# 001_MCU.net
KiCad netlist of a schematic drawn in Altium Designer
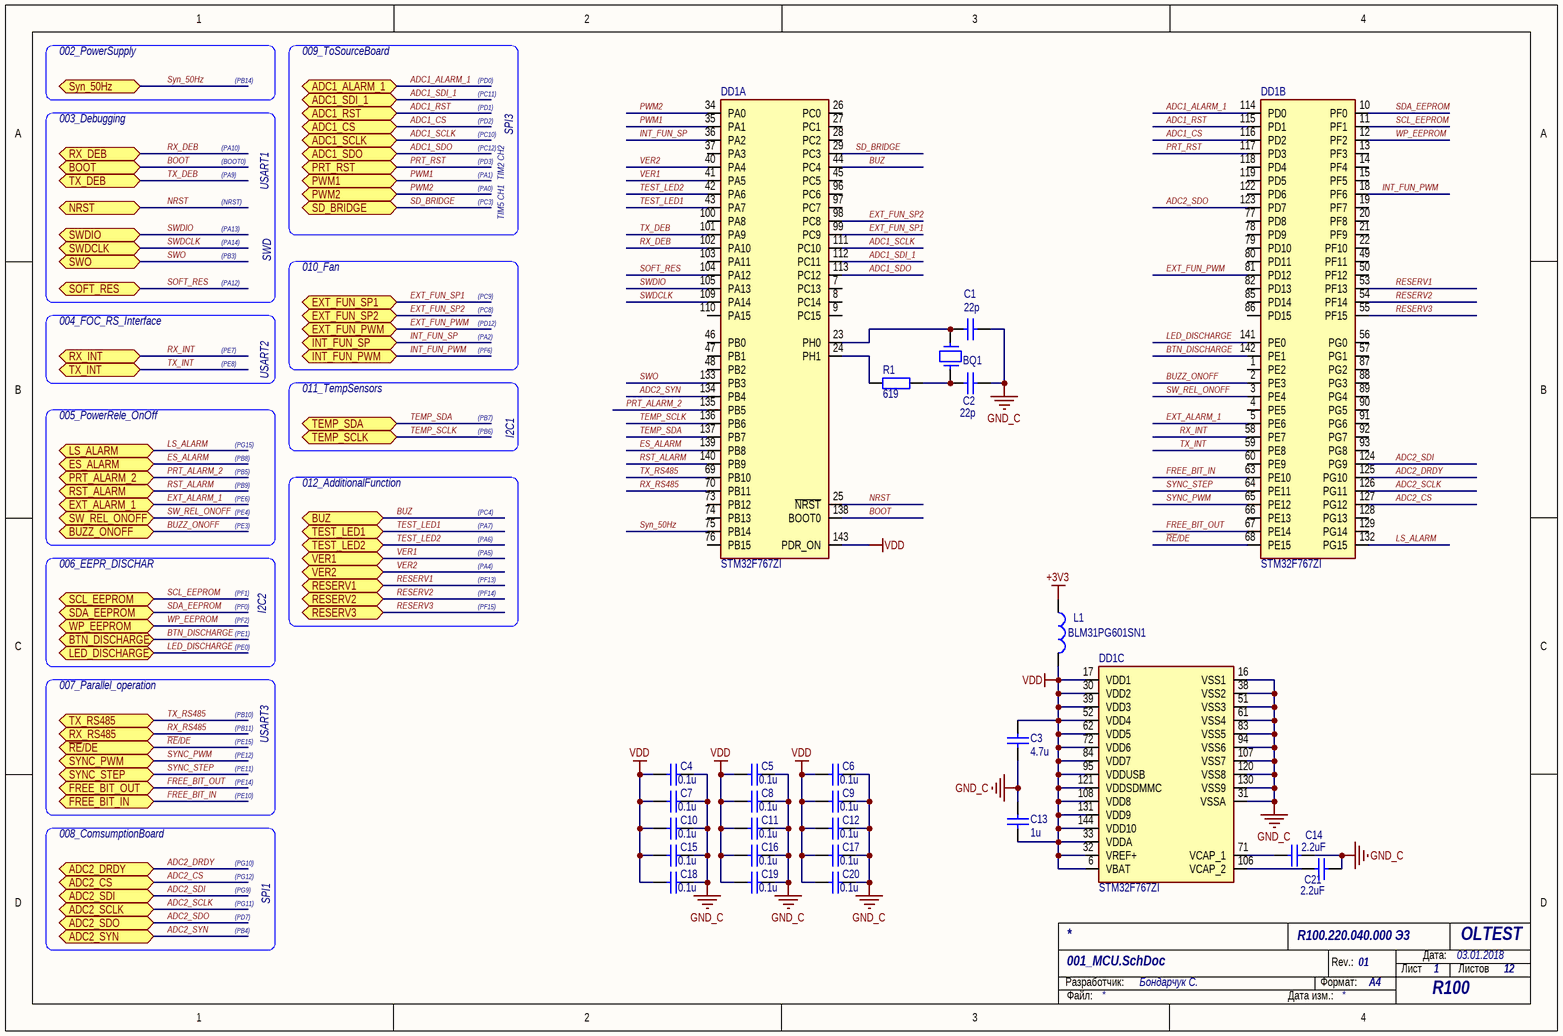
[diagram p0: 001_MCU.SchDoc]

(export (version "E")
  (design (tool "Eeschema 10.0.6"))
  (components
    (comp (ref "BQ1")
      (value "12MHz")
      (footprint "mainLib:DFN390P500X135-2N")
      (description "12MHz Quartz Crystal 7A")
      (fields (field (name "PARTNUMBER") "7A-12.000MAAJ-T") (field (name "MANUFACTURER") "TXC"))
      (libsource (lib "mainLib") (part "7A-12.000MAAJ-T"))
    )
    (comp (ref "C1")
      (value "22р")
      (footprint "mainLib:SMD_C_0603")
      (description "SMD C 0603 MURATA 50V 5% C0G")
      (fields (field (name "PARTNUMBER") "GRM1885C1H220JA01") (field (name "MANUFACTURER") "MURATA"))
      (libsource (lib "mainRCLib") (part "C0603 22p 50V 5%"))
    )
    (comp (ref "C2")
      (value "22р")
      (footprint "mainLib:SMD_C_0603")
      (description "SMD C 0603 MURATA 50V 5% C0G")
      (fields (field (name "PARTNUMBER") "GRM1885C1H220JA01") (field (name "MANUFACTURER") "MURATA"))
      (libsource (lib "mainRCLib") (part "C0603 22p 50V 5%"))
    )
    (comp (ref "C3")
      (value "4.7u")
      (footprint "mainLib:SMD_C_0805")
      (description "SMD C 0805 MURATA 50V 5% NP0")
      (fields (field (name "PARTNUMBER") "GRM21BR61E475M") (field (name "MANUFACTURER") "MURATA"))
      (libsource (lib "mainRCLib") (part "C0805 4.7u 25V 20%  X5R"))
    )
    (comp (ref "C4")
      (value "0.1u")
      (footprint "mainLib:SMD_C_0603")
      (description "SMD C 0603 MURATA 50V 10% X7R")
      (fields (field (name "PARTNUMBER") "GRM188R71H104K") (field (name "MANUFACTURER") "MURATA"))
      (libsource (lib "mainRCLib") (part "C0603 0.1u 50V 10%"))
    )
    (comp (ref "C5")
      (value "0.1u")
      (footprint "mainLib:SMD_C_0603")
      (description "SMD C 0603 MURATA 50V 10% X7R")
      (fields (field (name "PARTNUMBER") "GRM188R71H104K") (field (name "MANUFACTURER") "MURATA"))
      (libsource (lib "mainRCLib") (part "C0603 0.1u 50V 10%"))
    )
    (comp (ref "C6")
      (value "0.1u")
      (footprint "mainLib:SMD_C_0603")
      (description "SMD C 0603 MURATA 50V 10% X7R")
      (fields (field (name "PARTNUMBER") "GRM188R71H104K") (field (name "MANUFACTURER") "MURATA"))
      (libsource (lib "mainRCLib") (part "C0603 0.1u 50V 10%"))
    )
    (comp (ref "C7")
      (value "0.1u")
      (footprint "mainLib:SMD_C_0603")
      (description "SMD C 0603 MURATA 50V 10% X7R")
      (fields (field (name "PARTNUMBER") "GRM188R71H104K") (field (name "MANUFACTURER") "MURATA"))
      (libsource (lib "mainRCLib") (part "C0603 0.1u 50V 10%"))
    )
    (comp (ref "C8")
      (value "0.1u")
      (footprint "mainLib:SMD_C_0603")
      (description "SMD C 0603 MURATA 50V 10% X7R")
      (fields (field (name "PARTNUMBER") "GRM188R71H104K") (field (name "MANUFACTURER") "MURATA"))
      (libsource (lib "mainRCLib") (part "C0603 0.1u 50V 10%"))
    )
    (comp (ref "C9")
      (value "0.1u")
      (footprint "mainLib:SMD_C_0603")
      (description "SMD C 0603 MURATA 50V 10% X7R")
      (fields (field (name "PARTNUMBER") "GRM188R71H104K") (field (name "MANUFACTURER") "MURATA"))
      (libsource (lib "mainRCLib") (part "C0603 0.1u 50V 10%"))
    )
    (comp (ref "C10")
      (value "0.1u")
      (footprint "mainLib:SMD_C_0603")
      (description "SMD C 0603 MURATA 50V 10% X7R")
      (fields (field (name "PARTNUMBER") "GRM188R71H104K") (field (name "MANUFACTURER") "MURATA"))
      (libsource (lib "mainRCLib") (part "C0603 0.1u 50V 10%"))
    )
    (comp (ref "C11")
      (value "0.1u")
      (footprint "mainLib:SMD_C_0603")
      (description "SMD C 0603 MURATA 50V 10% X7R")
      (fields (field (name "PARTNUMBER") "GRM188R71H104K") (field (name "MANUFACTURER") "MURATA"))
      (libsource (lib "mainRCLib") (part "C0603 0.1u 50V 10%"))
    )
    (comp (ref "C12")
      (value "0.1u")
      (footprint "mainLib:SMD_C_0603")
      (description "SMD C 0603 MURATA 50V 10% X7R")
      (fields (field (name "PARTNUMBER") "GRM188R71H104K") (field (name "MANUFACTURER") "MURATA"))
      (libsource (lib "mainRCLib") (part "C0603 0.1u 50V 10%"))
    )
    (comp (ref "C13")
      (value "1u")
      (footprint "mainLib:SMD_C_0603")
      (description "SMD C 0603 MURATA 25V 10% X7R")
      (fields (field (name "PARTNUMBER") "GRM188R71E105KA12") (field (name "MANUFACTURER") "MURATA"))
      (libsource (lib "mainRCLib") (part "C0603 1uF 25V 10%"))
    )
    (comp (ref "C14")
      (value "2.2uF")
      (footprint "mainLib:SMD_C_0805")
      (description "SMD C 0805 MURATA 25V 10% X7R")
      (fields (field (name "PARTNUMBER") "GRM21BR61H225M") (field (name "MANUFACTURER") "MURATA"))
      (libsource (lib "mainRCLib") (part "C0805 2.2u 25V 10% X7R"))
    )
    (comp (ref "C15")
      (value "0.1u")
      (footprint "mainLib:SMD_C_0603")
      (description "SMD C 0603 MURATA 50V 10% X7R")
      (fields (field (name "PARTNUMBER") "GRM188R71H104K") (field (name "MANUFACTURER") "MURATA"))
      (libsource (lib "mainRCLib") (part "C0603 0.1u 50V 10%"))
    )
    (comp (ref "C16")
      (value "0.1u")
      (footprint "mainLib:SMD_C_0603")
      (description "SMD C 0603 MURATA 50V 10% X7R")
      (fields (field (name "PARTNUMBER") "GRM188R71H104K") (field (name "MANUFACTURER") "MURATA"))
      (libsource (lib "mainRCLib") (part "C0603 0.1u 50V 10%"))
    )
    (comp (ref "C17")
      (value "0.1u")
      (footprint "mainLib:SMD_C_0603")
      (description "SMD C 0603 MURATA 50V 10% X7R")
      (fields (field (name "PARTNUMBER") "GRM188R71H104K") (field (name "MANUFACTURER") "MURATA"))
      (libsource (lib "mainRCLib") (part "C0603 0.1u 50V 10%"))
    )
    (comp (ref "C18")
      (value "0.1u")
      (footprint "mainLib:SMD_C_0603")
      (description "SMD C 0603 MURATA 50V 10% X7R")
      (fields (field (name "PARTNUMBER") "GRM188R71H104K") (field (name "MANUFACTURER") "MURATA"))
      (libsource (lib "mainRCLib") (part "C0603 0.1u 50V 10%"))
    )
    (comp (ref "C19")
      (value "0.1u")
      (footprint "mainLib:SMD_C_0603")
      (description "SMD C 0603 MURATA 50V 10% X7R")
      (fields (field (name "PARTNUMBER") "GRM188R71H104K") (field (name "MANUFACTURER") "MURATA"))
      (libsource (lib "mainRCLib") (part "C0603 0.1u 50V 10%"))
    )
    (comp (ref "C20")
      (value "0.1u")
      (footprint "mainLib:SMD_C_0603")
      (description "SMD C 0603 MURATA 50V 10% X7R")
      (fields (field (name "PARTNUMBER") "GRM188R71H104K") (field (name "MANUFACTURER") "MURATA"))
      (libsource (lib "mainRCLib") (part "C0603 0.1u 50V 10%"))
    )
    (comp (ref "C21")
      (value "2.2uF")
      (footprint "mainLib:SMD_C_0805")
      (description "SMD C 0805 MURATA 25V 10% X7R")
      (fields (field (name "PARTNUMBER") "GRM21BR61H225M") (field (name "MANUFACTURER") "MURATA"))
      (libsource (lib "mainRCLib") (part "C0805 2.2u 25V 10% X7R"))
    )
    (comp (ref "DD1")
      (value "STM32F767ZI")
      (footprint "mainLib:SOT486-1_V")
      (description "32-bit ARM Cortex-M7 MCU+FPU")
      (libsource (lib "mainLib") (part "STM32F767ZI"))
    )
    (comp (ref "L1")
      (value "BLM31PG601SN1")
      (footprint "mainLib:SMD_L_1206")
      (description "600R 1.5A (100MHz)")
      (fields (field (name "MANUFACTURER") "TDK"))
      (libsource (lib "mainLib") (part "BLM31PG601SN1"))
    )
    (comp (ref "R1")
      (value "619")
      (footprint "mainLib:SMD_R_0603")
      (description "SMD 0603 VISHAY 0.1W 75V 1% 100ppm")
      (fields (field (name "PARTNUMBER") "CRCW0603619RFK") (field (name "MANUFACTURER") "VISHAY"))
      (libsource (lib "mainRCLib") (part "R0603 619 1%"))
    )
  )
  (nets
    (net (code "1") (name "+3V3") (class "Default")
      (node (ref "L1") (pin "1") (pinfunction "1_1") (pintype "passive"))
    )
    (net (code "2") (name "/ADC1_ALARM_1") (class "Default")
      (node (ref "DD1") (pin "114") (pinfunction "PD0_114") (pintype "passive"))
    )
    (net (code "3") (name "/ADC1_CS") (class "Default")
      (node (ref "DD1") (pin "116") (pinfunction "PD2_116") (pintype "passive"))
    )
    (net (code "4") (name "/ADC1_RST") (class "Default")
      (node (ref "DD1") (pin "115") (pinfunction "PD1_115") (pintype "passive"))
    )
    (net (code "5") (name "/ADC1_SCLK") (class "Default")
      (node (ref "DD1") (pin "111") (pinfunction "PC10_111") (pintype "passive"))
    )
    (net (code "6") (name "/ADC1_SDI_1") (class "Default")
      (node (ref "DD1") (pin "112") (pinfunction "PC11_112") (pintype "passive"))
    )
    (net (code "7") (name "/ADC1_SDO") (class "Default")
      (node (ref "DD1") (pin "113") (pinfunction "PC12_113") (pintype "passive"))
    )
    (net (code "8") (name "/ADC2_CS") (class "Default")
      (node (ref "DD1") (pin "127") (pinfunction "PG12_127") (pintype "passive"))
    )
    (net (code "9") (name "/ADC2_DRDY") (class "Default")
      (node (ref "DD1") (pin "125") (pinfunction "PG10_125") (pintype "passive"))
    )
    (net (code "10") (name "/ADC2_SCLK") (class "Default")
      (node (ref "DD1") (pin "126") (pinfunction "PG11_126") (pintype "passive"))
    )
    (net (code "11") (name "/ADC2_SDI") (class "Default")
      (node (ref "DD1") (pin "124") (pinfunction "PG9_124") (pintype "passive"))
    )
    (net (code "12") (name "/ADC2_SDO") (class "Default")
      (node (ref "DD1") (pin "123") (pinfunction "PD7_123") (pintype "passive"))
    )
    (net (code "13") (name "/ADC2_SYN") (class "Default")
      (node (ref "DD1") (pin "134") (pinfunction "PB4_134") (pintype "passive"))
    )
    (net (code "14") (name "/BOOT") (class "Default")
      (node (ref "DD1") (pin "138") (pinfunction "BOOT0_138") (pintype "passive"))
    )
    (net (code "15") (name "/BTN_DISCHARGE") (class "Default")
      (node (ref "DD1") (pin "142") (pinfunction "PE1_142") (pintype "passive"))
    )
    (net (code "16") (name "/BUZ") (class "Default")
      (node (ref "DD1") (pin "44") (pinfunction "PC4_44") (pintype "passive"))
    )
    (net (code "17") (name "/BUZZ_ONOFF") (class "Default")
      (node (ref "DD1") (pin "2") (pinfunction "PE3_2") (pintype "passive"))
    )
    (net (code "18") (name "/ES_ALARM") (class "Default")
      (node (ref "DD1") (pin "139") (pinfunction "PB8_139") (pintype "passive"))
    )
    (net (code "19") (name "/EXT_ALARM_1") (class "Default")
      (node (ref "DD1") (pin "5") (pinfunction "PE6_5") (pintype "passive"))
    )
    (net (code "20") (name "/EXT_FUN_PWM") (class "Default")
      (node (ref "DD1") (pin "81") (pinfunction "PD12_81") (pintype "passive"))
    )
    (net (code "21") (name "/EXT_FUN_SP1") (class "Default")
      (node (ref "DD1") (pin "99") (pinfunction "PC9_99") (pintype "passive"))
    )
    (net (code "22") (name "/EXT_FUN_SP2") (class "Default")
      (node (ref "DD1") (pin "98") (pinfunction "PC8_98") (pintype "passive"))
    )
    (net (code "23") (name "/FREE_BIT_IN") (class "Default")
      (node (ref "DD1") (pin "63") (pinfunction "PE10_63") (pintype "passive"))
    )
    (net (code "24") (name "/FREE_BIT_OUT") (class "Default")
      (node (ref "DD1") (pin "67") (pinfunction "PE14_67") (pintype "passive"))
    )
    (net (code "25") (name "/INT_FUN_PWM") (class "Default")
      (node (ref "DD1") (pin "18") (pinfunction "PF6_18") (pintype "passive"))
    )
    (net (code "26") (name "/INT_FUN_SP") (class "Default")
      (node (ref "DD1") (pin "36") (pinfunction "PA2_36") (pintype "passive"))
    )
    (net (code "27") (name "/LED_DISCHARGE") (class "Default")
      (node (ref "DD1") (pin "141") (pinfunction "PE0_141") (pintype "passive"))
    )
    (net (code "28") (name "/LS_ALARM") (class "Default")
      (node (ref "DD1") (pin "132") (pinfunction "PG15_132") (pintype "passive"))
    )
    (net (code "29") (name "/NRST") (class "Default")
      (node (ref "DD1") (pin "25") (pinfunction "~{NRST}_25") (pintype "passive"))
    )
    (net (code "30") (name "/PRT_ALARM_2") (class "Default")
      (node (ref "DD1") (pin "135") (pinfunction "PB5_135") (pintype "passive"))
    )
    (net (code "31") (name "/PRT_RST") (class "Default")
      (node (ref "DD1") (pin "117") (pinfunction "PD3_117") (pintype "passive"))
    )
    (net (code "32") (name "/PWM1") (class "Default")
      (node (ref "DD1") (pin "35") (pinfunction "PA1_35") (pintype "passive"))
    )
    (net (code "33") (name "/PWM2") (class "Default")
      (node (ref "DD1") (pin "34") (pinfunction "PA0_34") (pintype "passive"))
    )
    (net (code "34") (name "/RESERV1") (class "Default")
      (node (ref "DD1") (pin "53") (pinfunction "PF13_53") (pintype "passive"))
    )
    (net (code "35") (name "/RESERV2") (class "Default")
      (node (ref "DD1") (pin "54") (pinfunction "PF14_54") (pintype "passive"))
    )
    (net (code "36") (name "/RESERV3") (class "Default")
      (node (ref "DD1") (pin "55") (pinfunction "PF15_55") (pintype "passive"))
    )
    (net (code "37") (name "/RST_ALARM") (class "Default")
      (node (ref "DD1") (pin "140") (pinfunction "PB9_140") (pintype "passive"))
    )
    (net (code "38") (name "/RX_DEB") (class "Default")
      (node (ref "DD1") (pin "102") (pinfunction "PA10_102") (pintype "passive"))
    )
    (net (code "39") (name "/RX_INT") (class "Default")
      (node (ref "DD1") (pin "58") (pinfunction "PE7_58") (pintype "passive"))
    )
    (net (code "40") (name "/RX_RS485") (class "Default")
      (node (ref "DD1") (pin "70") (pinfunction "PB11_70") (pintype "passive"))
    )
    (net (code "41") (name "/SCL_EEPROM") (class "Default")
      (node (ref "DD1") (pin "11") (pinfunction "PF1_11") (pintype "passive"))
    )
    (net (code "42") (name "/SDA_EEPROM") (class "Default")
      (node (ref "DD1") (pin "10") (pinfunction "PF0_10") (pintype "passive"))
    )
    (net (code "43") (name "/SD_BRIDGE") (class "Default")
      (node (ref "DD1") (pin "29") (pinfunction "PC3_29") (pintype "passive"))
    )
    (net (code "44") (name "/SOFT_RES") (class "Default")
      (node (ref "DD1") (pin "104") (pinfunction "PA12_104") (pintype "passive"))
    )
    (net (code "45") (name "/SWDCLK") (class "Default")
      (node (ref "DD1") (pin "109") (pinfunction "PA14_109") (pintype "passive"))
    )
    (net (code "46") (name "/SWDIO") (class "Default")
      (node (ref "DD1") (pin "105") (pinfunction "PA13_105") (pintype "passive"))
    )
    (net (code "47") (name "/SWO") (class "Default")
      (node (ref "DD1") (pin "133") (pinfunction "PB3_133") (pintype "passive"))
    )
    (net (code "48") (name "/SW_REL_ONOFF") (class "Default")
      (node (ref "DD1") (pin "3") (pinfunction "PE4_3") (pintype "passive"))
    )
    (net (code "49") (name "/SYNC_PWM") (class "Default")
      (node (ref "DD1") (pin "65") (pinfunction "PE12_65") (pintype "passive"))
    )
    (net (code "50") (name "/SYNC_STEP") (class "Default")
      (node (ref "DD1") (pin "64") (pinfunction "PE11_64") (pintype "passive"))
    )
    (net (code "51") (name "/Syn_50Hz") (class "Default")
      (node (ref "DD1") (pin "75") (pinfunction "PB14_75") (pintype "passive"))
    )
    (net (code "52") (name "/TEMP_SCLK") (class "Default")
      (node (ref "DD1") (pin "136") (pinfunction "PB6_136") (pintype "passive"))
    )
    (net (code "53") (name "/TEMP_SDA") (class "Default")
      (node (ref "DD1") (pin "137") (pinfunction "PB7_137") (pintype "passive"))
    )
    (net (code "54") (name "/TEST_LED1") (class "Default")
      (node (ref "DD1") (pin "43") (pinfunction "PA7_43") (pintype "passive"))
    )
    (net (code "55") (name "/TEST_LED2") (class "Default")
      (node (ref "DD1") (pin "42") (pinfunction "PA6_42") (pintype "passive"))
    )
    (net (code "56") (name "/TX_DEB") (class "Default")
      (node (ref "DD1") (pin "101") (pinfunction "PA9_101") (pintype "passive"))
    )
    (net (code "57") (name "/TX_INT") (class "Default")
      (node (ref "DD1") (pin "59") (pinfunction "PE8_59") (pintype "passive"))
    )
    (net (code "58") (name "/TX_RS485") (class "Default")
      (node (ref "DD1") (pin "69") (pinfunction "PB10_69") (pintype "passive"))
    )
    (net (code "59") (name "/VER1") (class "Default")
      (node (ref "DD1") (pin "41") (pinfunction "PA5_41") (pintype "passive"))
    )
    (net (code "60") (name "/VER2") (class "Default")
      (node (ref "DD1") (pin "40") (pinfunction "PA4_40") (pintype "passive"))
    )
    (net (code "61") (name "/WP_EEPROM") (class "Default")
      (node (ref "DD1") (pin "12") (pinfunction "PF2_12") (pintype "passive"))
    )
    (net (code "62") (name "/~{RE}{slash}DE") (class "Default")
      (node (ref "DD1") (pin "68") (pinfunction "PE15_68") (pintype "passive"))
    )
    (net (code "63") (name "GND_C") (class "Default")
      (node (ref "C1") (pin "2") (pinfunction "2_2") (pintype "passive"))
      (node (ref "C10") (pin "2") (pinfunction "2_2") (pintype "passive"))
      (node (ref "C11") (pin "2") (pinfunction "2_2") (pintype "passive"))
      (node (ref "C12") (pin "2") (pinfunction "2_2") (pintype "passive"))
      (node (ref "C13") (pin "2") (pinfunction "2_2") (pintype "passive"))
      (node (ref "C14") (pin "2") (pinfunction "2_2") (pintype "passive"))
      (node (ref "C15") (pin "2") (pinfunction "2_2") (pintype "passive"))
      (node (ref "C16") (pin "2") (pinfunction "2_2") (pintype "passive"))
      (node (ref "C17") (pin "2") (pinfunction "2_2") (pintype "passive"))
      (node (ref "C18") (pin "2") (pinfunction "2_2") (pintype "passive"))
      (node (ref "C19") (pin "2") (pinfunction "2_2") (pintype "passive"))
      (node (ref "C2") (pin "2") (pinfunction "2_2") (pintype "passive"))
      (node (ref "C20") (pin "2") (pinfunction "2_2") (pintype "passive"))
      (node (ref "C21") (pin "2") (pinfunction "2_2") (pintype "passive"))
      (node (ref "C3") (pin "1") (pinfunction "1_1") (pintype "passive"))
      (node (ref "C4") (pin "2") (pinfunction "2_2") (pintype "passive"))
      (node (ref "C5") (pin "2") (pinfunction "2_2") (pintype "passive"))
      (node (ref "C6") (pin "2") (pinfunction "2_2") (pintype "passive"))
      (node (ref "C7") (pin "2") (pinfunction "2_2") (pintype "passive"))
      (node (ref "C8") (pin "2") (pinfunction "2_2") (pintype "passive"))
      (node (ref "C9") (pin "2") (pinfunction "2_2") (pintype "passive"))
      (node (ref "DD1") (pin "107") (pinfunction "VSS7_107") (pintype "passive"))
      (node (ref "DD1") (pin "120") (pinfunction "VSS8_120") (pintype "passive"))
      (node (ref "DD1") (pin "130") (pinfunction "VSS9_130") (pintype "passive"))
      (node (ref "DD1") (pin "16") (pinfunction "VSS1_16") (pintype "passive"))
      (node (ref "DD1") (pin "31") (pinfunction "VSSA_31") (pintype "passive"))
      (node (ref "DD1") (pin "38") (pinfunction "VSS2_38") (pintype "passive"))
      (node (ref "DD1") (pin "51") (pinfunction "VSS3_51") (pintype "passive"))
      (node (ref "DD1") (pin "61") (pinfunction "VSS4_61") (pintype "passive"))
      (node (ref "DD1") (pin "83") (pinfunction "VSS5_83") (pintype "passive"))
      (node (ref "DD1") (pin "94") (pinfunction "VSS6_94") (pintype "passive"))
    )
    (net (code "64") (name "Net-(BQ1-Pad1)") (class "Default")
      (node (ref "BQ1") (pin "1") (pinfunction "1_1") (pintype "passive"))
      (node (ref "C2") (pin "1") (pinfunction "1_1") (pintype "passive"))
      (node (ref "R1") (pin "2") (pinfunction "2_2") (pintype "passive"))
    )
    (net (code "65") (name "Net-(DD1A-PH0)") (class "Default")
      (node (ref "BQ1") (pin "2") (pinfunction "2_2") (pintype "passive"))
      (node (ref "C1") (pin "1") (pinfunction "1_1") (pintype "passive"))
      (node (ref "DD1") (pin "23") (pinfunction "PH0_23") (pintype "passive"))
    )
    (net (code "66") (name "Net-(DD1A-PH1)") (class "Default")
      (node (ref "DD1") (pin "24") (pinfunction "PH1_24") (pintype "passive"))
      (node (ref "R1") (pin "1") (pinfunction "1_1") (pintype "passive"))
    )
    (net (code "67") (name "Net-(DD1C-VCAP_1)") (class "Default")
      (node (ref "C14") (pin "1") (pinfunction "1_1") (pintype "passive"))
      (node (ref "DD1") (pin "71") (pinfunction "VCAP_1_71") (pintype "passive"))
    )
    (net (code "68") (name "Net-(DD1C-VCAP_2)") (class "Default")
      (node (ref "C21") (pin "1") (pinfunction "1_1") (pintype "passive"))
      (node (ref "DD1") (pin "106") (pinfunction "VCAP_2_106") (pintype "passive"))
    )
    (net (code "69") (name "VDD") (class "Default")
      (node (ref "C10") (pin "1") (pinfunction "1_1") (pintype "passive"))
      (node (ref "C11") (pin "1") (pinfunction "1_1") (pintype "passive"))
      (node (ref "C12") (pin "1") (pinfunction "1_1") (pintype "passive"))
      (node (ref "C13") (pin "1") (pinfunction "1_1") (pintype "passive"))
      (node (ref "C15") (pin "1") (pinfunction "1_1") (pintype "passive"))
      (node (ref "C16") (pin "1") (pinfunction "1_1") (pintype "passive"))
      (node (ref "C17") (pin "1") (pinfunction "1_1") (pintype "passive"))
      (node (ref "C18") (pin "1") (pinfunction "1_1") (pintype "passive"))
      (node (ref "C19") (pin "1") (pinfunction "1_1") (pintype "passive"))
      (node (ref "C20") (pin "1") (pinfunction "1_1") (pintype "passive"))
      (node (ref "C3") (pin "2") (pinfunction "2_2") (pintype "passive"))
      (node (ref "C4") (pin "1") (pinfunction "1_1") (pintype "passive"))
      (node (ref "C5") (pin "1") (pinfunction "1_1") (pintype "passive"))
      (node (ref "C6") (pin "1") (pinfunction "1_1") (pintype "passive"))
      (node (ref "C7") (pin "1") (pinfunction "1_1") (pintype "passive"))
      (node (ref "C8") (pin "1") (pinfunction "1_1") (pintype "passive"))
      (node (ref "C9") (pin "1") (pinfunction "1_1") (pintype "passive"))
      (node (ref "DD1") (pin "108") (pinfunction "VDD8_108") (pintype "passive"))
      (node (ref "DD1") (pin "121") (pinfunction "VDDSDMMC_121") (pintype "passive"))
      (node (ref "DD1") (pin "131") (pinfunction "VDD9_131") (pintype "passive"))
      (node (ref "DD1") (pin "143") (pinfunction "PDR_ON_143") (pintype "passive"))
      (node (ref "DD1") (pin "144") (pinfunction "VDD10_144") (pintype "passive"))
      (node (ref "DD1") (pin "17") (pinfunction "VDD1_17") (pintype "passive"))
      (node (ref "DD1") (pin "30") (pinfunction "VDD2_30") (pintype "passive"))
      (node (ref "DD1") (pin "32") (pinfunction "VREF+_32") (pintype "passive"))
      (node (ref "DD1") (pin "33") (pinfunction "VDDA_33") (pintype "passive"))
      (node (ref "DD1") (pin "39") (pinfunction "VDD3_39") (pintype "passive"))
      (node (ref "DD1") (pin "52") (pinfunction "VDD4_52") (pintype "passive"))
      (node (ref "DD1") (pin "6") (pinfunction "VBAT_6") (pintype "passive"))
      (node (ref "DD1") (pin "62") (pinfunction "VDD5_62") (pintype "passive"))
      (node (ref "DD1") (pin "72") (pinfunction "VDD6_72") (pintype "passive"))
      (node (ref "DD1") (pin "84") (pinfunction "VDD7_84") (pintype "passive"))
      (node (ref "DD1") (pin "95") (pinfunction "VDDUSB_95") (pintype "passive"))
      (node (ref "L1") (pin "2") (pinfunction "2_2") (pintype "passive"))
    )
    (net (code "70") (name "unconnected-(DD1A-PA3-Pad37)") (class "Default")
      (node (ref "DD1") (pin "37") (pinfunction "PA3_37") (pintype "passive"))
    )
    (net (code "71") (name "unconnected-(DD1A-PA8-Pad100)") (class "Default")
      (node (ref "DD1") (pin "100") (pinfunction "PA8_100") (pintype "passive"))
    )
    (net (code "72") (name "unconnected-(DD1A-PA11-Pad103)") (class "Default")
      (node (ref "DD1") (pin "103") (pinfunction "PA11_103") (pintype "passive"))
    )
    (net (code "73") (name "unconnected-(DD1A-PA15-Pad110)") (class "Default")
      (node (ref "DD1") (pin "110") (pinfunction "PA15_110") (pintype "passive"))
    )
    (net (code "74") (name "unconnected-(DD1A-PB0-Pad46)") (class "Default")
      (node (ref "DD1") (pin "46") (pinfunction "PB0_46") (pintype "passive"))
    )
    (net (code "75") (name "unconnected-(DD1A-PB1-Pad47)") (class "Default")
      (node (ref "DD1") (pin "47") (pinfunction "PB1_47") (pintype "passive"))
    )
    (net (code "76") (name "unconnected-(DD1A-PB2-Pad48)") (class "Default")
      (node (ref "DD1") (pin "48") (pinfunction "PB2_48") (pintype "passive"))
    )
    (net (code "77") (name "unconnected-(DD1A-PB12-Pad73)") (class "Default")
      (node (ref "DD1") (pin "73") (pinfunction "PB12_73") (pintype "passive"))
    )
    (net (code "78") (name "unconnected-(DD1A-PB13-Pad74)") (class "Default")
      (node (ref "DD1") (pin "74") (pinfunction "PB13_74") (pintype "passive"))
    )
    (net (code "79") (name "unconnected-(DD1A-PB15-Pad76)") (class "Default")
      (node (ref "DD1") (pin "76") (pinfunction "PB15_76") (pintype "passive"))
    )
    (net (code "80") (name "unconnected-(DD1A-PC0-Pad26)") (class "Default")
      (node (ref "DD1") (pin "26") (pinfunction "PC0_26") (pintype "passive"))
    )
    (net (code "81") (name "unconnected-(DD1A-PC1-Pad27)") (class "Default")
      (node (ref "DD1") (pin "27") (pinfunction "PC1_27") (pintype "passive"))
    )
    (net (code "82") (name "unconnected-(DD1A-PC2-Pad28)") (class "Default")
      (node (ref "DD1") (pin "28") (pinfunction "PC2_28") (pintype "passive"))
    )
    (net (code "83") (name "unconnected-(DD1A-PC5-Pad45)") (class "Default")
      (node (ref "DD1") (pin "45") (pinfunction "PC5_45") (pintype "passive"))
    )
    (net (code "84") (name "unconnected-(DD1A-PC6-Pad96)") (class "Default")
      (node (ref "DD1") (pin "96") (pinfunction "PC6_96") (pintype "passive"))
    )
    (net (code "85") (name "unconnected-(DD1A-PC7-Pad97)") (class "Default")
      (node (ref "DD1") (pin "97") (pinfunction "PC7_97") (pintype "passive"))
    )
    (net (code "86") (name "unconnected-(DD1A-PC13-Pad7)") (class "Default")
      (node (ref "DD1") (pin "7") (pinfunction "PC13_7") (pintype "passive"))
    )
    (net (code "87") (name "unconnected-(DD1A-PC14-Pad8)") (class "Default")
      (node (ref "DD1") (pin "8") (pinfunction "PC14_8") (pintype "passive"))
    )
    (net (code "88") (name "unconnected-(DD1A-PC15-Pad9)") (class "Default")
      (node (ref "DD1") (pin "9") (pinfunction "PC15_9") (pintype "passive"))
    )
    (net (code "89") (name "unconnected-(DD1B-PD4-Pad118)") (class "Default")
      (node (ref "DD1") (pin "118") (pinfunction "PD4_118") (pintype "passive"))
    )
    (net (code "90") (name "unconnected-(DD1B-PD5-Pad119)") (class "Default")
      (node (ref "DD1") (pin "119") (pinfunction "PD5_119") (pintype "passive"))
    )
    (net (code "91") (name "unconnected-(DD1B-PD6-Pad122)") (class "Default")
      (node (ref "DD1") (pin "122") (pinfunction "PD6_122") (pintype "passive"))
    )
    (net (code "92") (name "unconnected-(DD1B-PD8-Pad77)") (class "Default")
      (node (ref "DD1") (pin "77") (pinfunction "PD8_77") (pintype "passive"))
    )
    (net (code "93") (name "unconnected-(DD1B-PD9-Pad78)") (class "Default")
      (node (ref "DD1") (pin "78") (pinfunction "PD9_78") (pintype "passive"))
    )
    (net (code "94") (name "unconnected-(DD1B-PD10-Pad79)") (class "Default")
      (node (ref "DD1") (pin "79") (pinfunction "PD10_79") (pintype "passive"))
    )
    (net (code "95") (name "unconnected-(DD1B-PD11-Pad80)") (class "Default")
      (node (ref "DD1") (pin "80") (pinfunction "PD11_80") (pintype "passive"))
    )
    (net (code "96") (name "unconnected-(DD1B-PD13-Pad82)") (class "Default")
      (node (ref "DD1") (pin "82") (pinfunction "PD13_82") (pintype "passive"))
    )
    (net (code "97") (name "unconnected-(DD1B-PD14-Pad85)") (class "Default")
      (node (ref "DD1") (pin "85") (pinfunction "PD14_85") (pintype "passive"))
    )
    (net (code "98") (name "unconnected-(DD1B-PD15-Pad86)") (class "Default")
      (node (ref "DD1") (pin "86") (pinfunction "PD15_86") (pintype "passive"))
    )
    (net (code "99") (name "unconnected-(DD1B-PE2-Pad1)") (class "Default")
      (node (ref "DD1") (pin "1") (pinfunction "PE2_1") (pintype "passive"))
    )
    (net (code "100") (name "unconnected-(DD1B-PE5-Pad4)") (class "Default")
      (node (ref "DD1") (pin "4") (pinfunction "PE5_4") (pintype "passive"))
    )
    (net (code "101") (name "unconnected-(DD1B-PE9-Pad60)") (class "Default")
      (node (ref "DD1") (pin "60") (pinfunction "PE9_60") (pintype "passive"))
    )
    (net (code "102") (name "unconnected-(DD1B-PE13-Pad66)") (class "Default")
      (node (ref "DD1") (pin "66") (pinfunction "PE13_66") (pintype "passive"))
    )
    (net (code "103") (name "unconnected-(DD1B-PF3-Pad13)") (class "Default")
      (node (ref "DD1") (pin "13") (pinfunction "PF3_13") (pintype "passive"))
    )
    (net (code "104") (name "unconnected-(DD1B-PF4-Pad14)") (class "Default")
      (node (ref "DD1") (pin "14") (pinfunction "PF4_14") (pintype "passive"))
    )
    (net (code "105") (name "unconnected-(DD1B-PF5-Pad15)") (class "Default")
      (node (ref "DD1") (pin "15") (pinfunction "PF5_15") (pintype "passive"))
    )
    (net (code "106") (name "unconnected-(DD1B-PF7-Pad19)") (class "Default")
      (node (ref "DD1") (pin "19") (pinfunction "PF7_19") (pintype "passive"))
    )
    (net (code "107") (name "unconnected-(DD1B-PF8-Pad20)") (class "Default")
      (node (ref "DD1") (pin "20") (pinfunction "PF8_20") (pintype "passive"))
    )
    (net (code "108") (name "unconnected-(DD1B-PF9-Pad21)") (class "Default")
      (node (ref "DD1") (pin "21") (pinfunction "PF9_21") (pintype "passive"))
    )
    (net (code "109") (name "unconnected-(DD1B-PF10-Pad22)") (class "Default")
      (node (ref "DD1") (pin "22") (pinfunction "PF10_22") (pintype "passive"))
    )
    (net (code "110") (name "unconnected-(DD1B-PF11-Pad49)") (class "Default")
      (node (ref "DD1") (pin "49") (pinfunction "PF11_49") (pintype "passive"))
    )
    (net (code "111") (name "unconnected-(DD1B-PF12-Pad50)") (class "Default")
      (node (ref "DD1") (pin "50") (pinfunction "PF12_50") (pintype "passive"))
    )
    (net (code "112") (name "unconnected-(DD1B-PG0-Pad56)") (class "Default")
      (node (ref "DD1") (pin "56") (pinfunction "PG0_56") (pintype "passive"))
    )
    (net (code "113") (name "unconnected-(DD1B-PG1-Pad57)") (class "Default")
      (node (ref "DD1") (pin "57") (pinfunction "PG1_57") (pintype "passive"))
    )
    (net (code "114") (name "unconnected-(DD1B-PG2-Pad87)") (class "Default")
      (node (ref "DD1") (pin "87") (pinfunction "PG2_87") (pintype "passive"))
    )
    (net (code "115") (name "unconnected-(DD1B-PG3-Pad88)") (class "Default")
      (node (ref "DD1") (pin "88") (pinfunction "PG3_88") (pintype "passive"))
    )
    (net (code "116") (name "unconnected-(DD1B-PG4-Pad89)") (class "Default")
      (node (ref "DD1") (pin "89") (pinfunction "PG4_89") (pintype "passive"))
    )
    (net (code "117") (name "unconnected-(DD1B-PG5-Pad90)") (class "Default")
      (node (ref "DD1") (pin "90") (pinfunction "PG5_90") (pintype "passive"))
    )
    (net (code "118") (name "unconnected-(DD1B-PG6-Pad91)") (class "Default")
      (node (ref "DD1") (pin "91") (pinfunction "PG6_91") (pintype "passive"))
    )
    (net (code "119") (name "unconnected-(DD1B-PG7-Pad92)") (class "Default")
      (node (ref "DD1") (pin "92") (pinfunction "PG7_92") (pintype "passive"))
    )
    (net (code "120") (name "unconnected-(DD1B-PG8-Pad93)") (class "Default")
      (node (ref "DD1") (pin "93") (pinfunction "PG8_93") (pintype "passive"))
    )
    (net (code "121") (name "unconnected-(DD1B-PG13-Pad128)") (class "Default")
      (node (ref "DD1") (pin "128") (pinfunction "PG13_128") (pintype "passive"))
    )
    (net (code "122") (name "unconnected-(DD1B-PG14-Pad129)") (class "Default")
      (node (ref "DD1") (pin "129") (pinfunction "PG14_129") (pintype "passive"))
    )
  )
)
